# IHM_BUTTONS.net
KiCad netlist of a schematic drawn in EAGLE
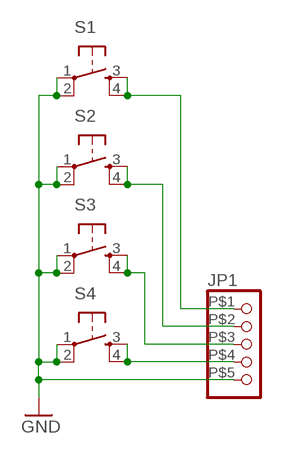
[diagram p0: schematic, sheet 1]

(export (version "E")
  (design (tool "Eeschema 10.0.6"))
  (components
    (comp (ref "JP1")
      (value "PINHD-1X05_2.54-SMD-WIRE")
      (footprint "eagle-import:1X05WIRE")
      (libsource (lib "eagle-import") (part "PINHD-1X05_2.54-SMD-WIRE"))
    )
    (comp (ref "S1")
      (value "6MM_SWITCH6MM_SWITCH")
      (footprint "eagle-import:6MM_SWITCH")
      (libsource (lib "eagle-import") (part "6MM_SWITCH6MM_SWITCH"))
    )
    (comp (ref "S2")
      (value "6MM_SWITCH6MM_SWITCH")
      (footprint "eagle-import:6MM_SWITCH")
      (libsource (lib "eagle-import") (part "6MM_SWITCH6MM_SWITCH"))
    )
    (comp (ref "S3")
      (value "6MM_SWITCH6MM_SWITCH")
      (footprint "eagle-import:6MM_SWITCH")
      (libsource (lib "eagle-import") (part "6MM_SWITCH6MM_SWITCH"))
    )
    (comp (ref "S4")
      (value "6MM_SWITCH6MM_SWITCH")
      (footprint "eagle-import:6MM_SWITCH")
      (libsource (lib "eagle-import") (part "6MM_SWITCH6MM_SWITCH"))
    )
  )
  (nets
    (net (code "1") (name "GND") (class "Default")
      (node (ref "JP1") (pin "P$5") (pinfunction "5_P$5") (pintype "passive"))
      (node (ref "S1") (pin "1") (pinfunction "P_1") (pintype "passive"))
      (node (ref "S1") (pin "2") (pinfunction "P1_2") (pintype "passive"))
      (node (ref "S2") (pin "1") (pinfunction "P_1") (pintype "passive"))
      (node (ref "S2") (pin "2") (pinfunction "P1_2") (pintype "passive"))
      (node (ref "S3") (pin "1") (pinfunction "P_1") (pintype "passive"))
      (node (ref "S3") (pin "2") (pinfunction "P1_2") (pintype "passive"))
      (node (ref "S4") (pin "1") (pinfunction "P_1") (pintype "passive"))
      (node (ref "S4") (pin "2") (pinfunction "P1_2") (pintype "passive"))
    )
    (net (code "2") (name "Net-(JP1-1)") (class "Default")
      (node (ref "JP1") (pin "P$1") (pinfunction "1_P$1") (pintype "passive"))
      (node (ref "S1") (pin "3") (pinfunction "S_3") (pintype "passive"))
      (node (ref "S1") (pin "4") (pinfunction "S1_4") (pintype "passive"))
    )
    (net (code "3") (name "Net-(JP1-2)") (class "Default")
      (node (ref "JP1") (pin "P$2") (pinfunction "2_P$2") (pintype "passive"))
      (node (ref "S2") (pin "3") (pinfunction "S_3") (pintype "passive"))
      (node (ref "S2") (pin "4") (pinfunction "S1_4") (pintype "passive"))
    )
    (net (code "4") (name "Net-(JP1-3)") (class "Default")
      (node (ref "JP1") (pin "P$3") (pinfunction "3_P$3") (pintype "passive"))
      (node (ref "S3") (pin "3") (pinfunction "S_3") (pintype "passive"))
      (node (ref "S3") (pin "4") (pinfunction "S1_4") (pintype "passive"))
    )
    (net (code "5") (name "Net-(JP1-4)") (class "Default")
      (node (ref "JP1") (pin "P$4") (pinfunction "4_P$4") (pintype "passive"))
      (node (ref "S4") (pin "3") (pinfunction "S_3") (pintype "passive"))
      (node (ref "S4") (pin "4") (pinfunction "S1_4") (pintype "passive"))
    )
  )
)
